# master_board_labrob.net
KiCad netlist of a schematic drawn in EAGLE
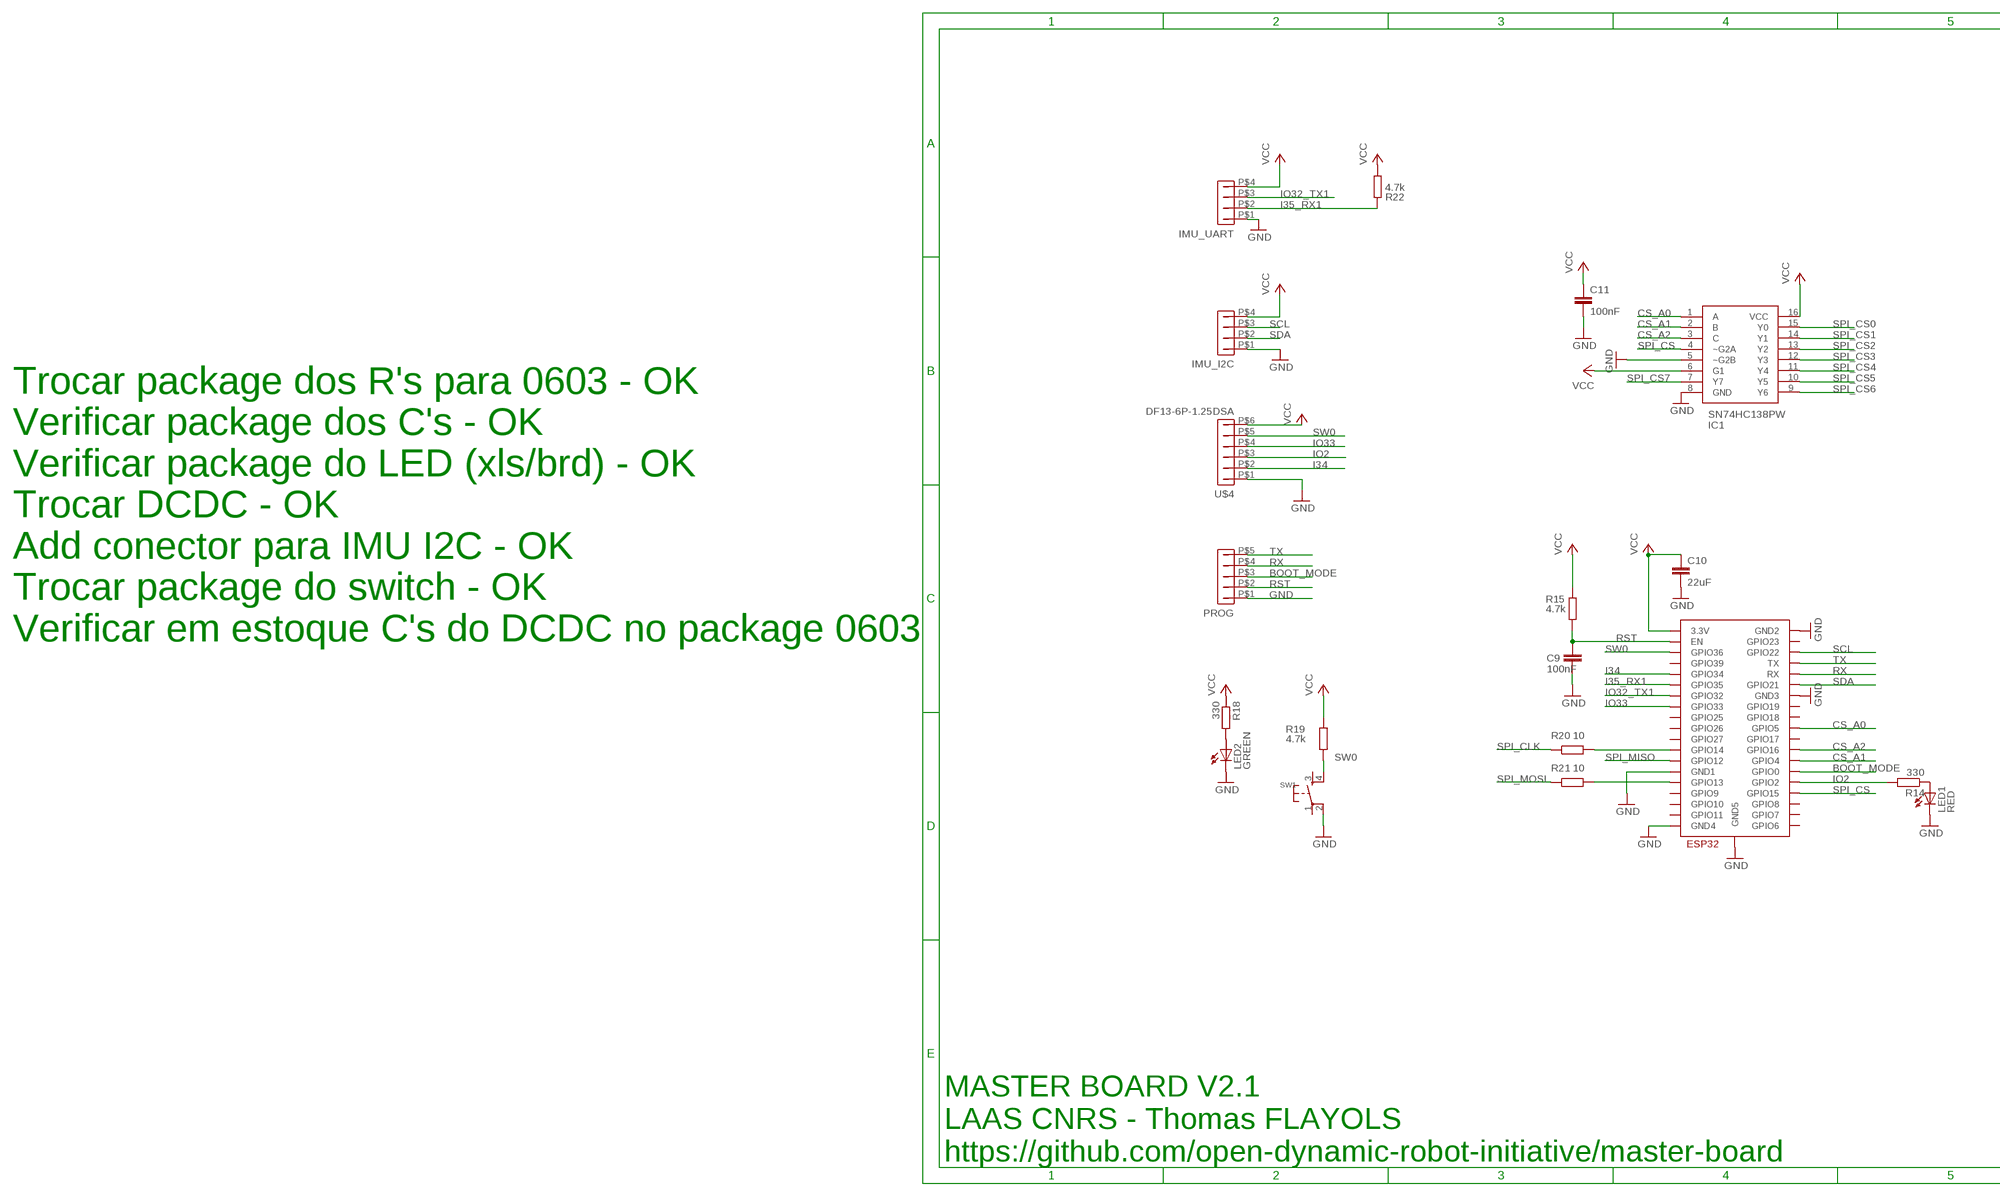
[diagram p0: schematic, sheet 1, part 1 of 2]
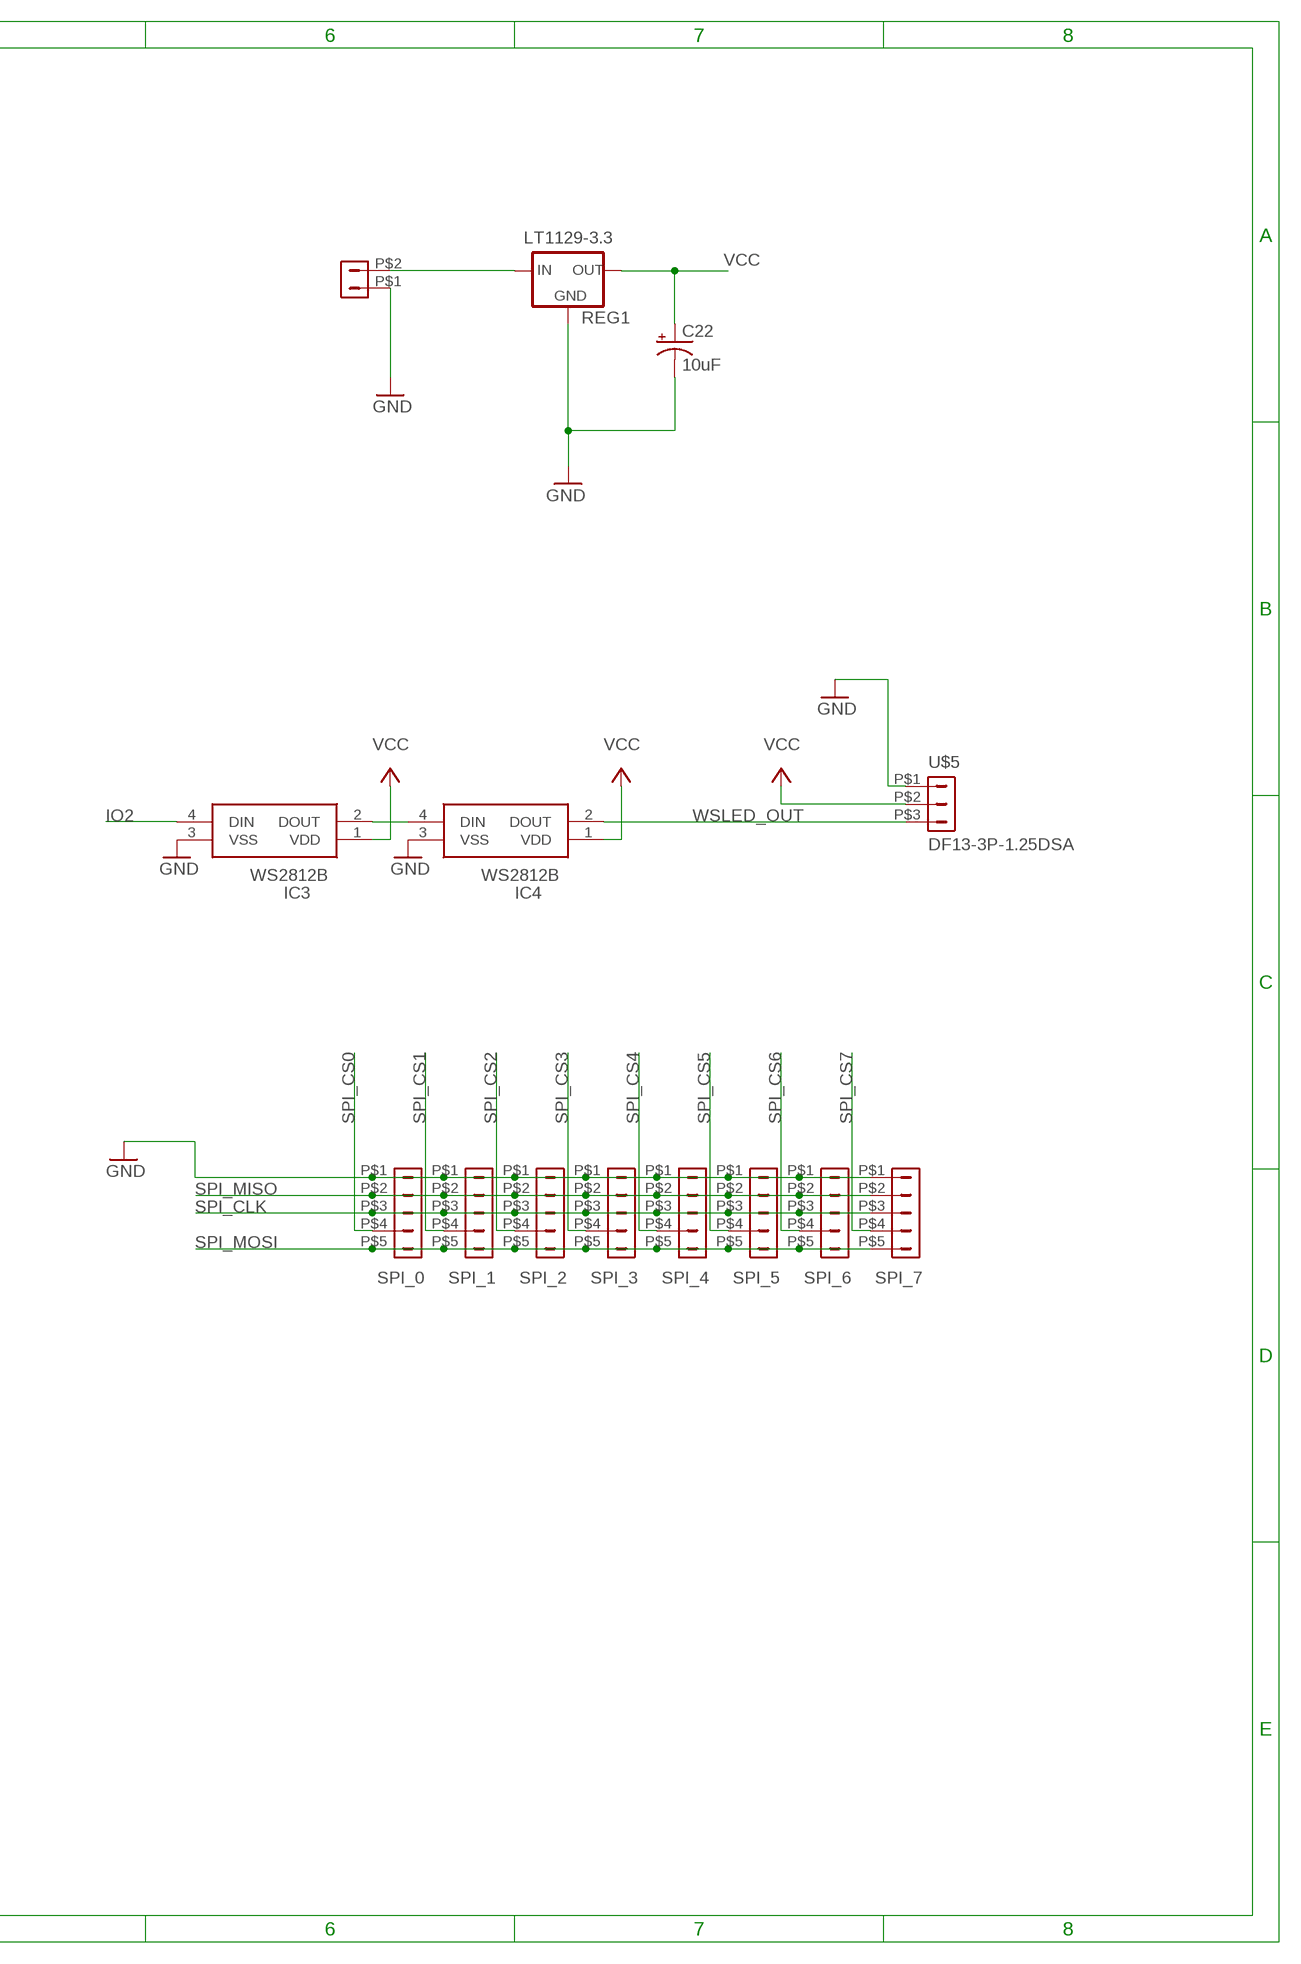
[diagram p1: schematic, sheet 1, part 2 of 2]

(export (version "E")
  (design (tool "Eeschema 10.0.6"))
  (components
    (comp (ref "C9")
      (value "100nF")
      (footprint "eagle-import:C0603")
      (fields (field (name "MANUFACTURER_PART_NUMBER") "CPL-CAP-X7R-0402-100NF-16V"))
      (libsource (lib "eagle-import") (part "C-EUC0603"))
    )
    (comp (ref "C10")
      (value "22uF")
      (footprint "eagle-import:C0805")
      (fields (field (name "MANUFACTURER_PART_NUMBER") "CPL-CAP-X5R-0805-22UF-6.3V"))
      (libsource (lib "eagle-import") (part "C-EUC0805"))
    )
    (comp (ref "C11")
      (value "100nF")
      (footprint "eagle-import:C0603")
      (fields (field (name "MANUFACTURER_PART_NUMBER") "CPL-CAP-X7R-0402-100NF-16V"))
      (libsource (lib "eagle-import") (part "C-EUC0603"))
    )
    (comp (ref "C22")
      (value "10uF")
      (footprint "eagle-import:C_6032-28R")
      (libsource (lib "eagle-import") (part "CPOL-USC/6032-28R"))
    )
    (comp (ref "IC1")
      (value "SN74HC138PW")
      (footprint "eagle-import:SOP65P640X120-16N")
      (fields (field (name "RS_PART_NUMBER") "6631928"))
      (libsource (lib "eagle-import") (part "SN74HC138PW"))
    )
    (comp (ref "IC3")
      (value "WS2812B")
      (footprint "eagle-import:WS2812B")
      (libsource (lib "eagle-import") (part "WS2812B"))
    )
    (comp (ref "IC4")
      (value "WS2812B")
      (footprint "eagle-import:WS2812B")
      (libsource (lib "eagle-import") (part "WS2812B"))
    )
    (comp (ref "IMU_I2C")
      (value "DF13-4P-1.25DSA")
      (footprint "eagle-import:DF13-4P-1.25DSA")
      (libsource (lib "eagle-import") (part "DF13-4P-1.25DSA"))
    )
    (comp (ref "IMU_UART")
      (value "DF13-4P-1.25DSA")
      (footprint "eagle-import:DF13-4P-1.25DSA")
      (libsource (lib "eagle-import") (part "DF13-4P-1.25DSA"))
    )
    (comp (ref "LED1")
      (value "RED")
      (footprint "eagle-import:CHIPLED_0603")
      (fields (field (name "MANUFACTURER_PART_NUMBER") "CPL-LED-0603-RED"))
      (libsource (lib "eagle-import") (part "LEDCHIPLED_0603"))
    )
    (comp (ref "LED2")
      (value "GREEN")
      (footprint "eagle-import:CHIPLED_0603")
      (fields (field (name "MANUFACTURER_PART_NUMBER") "CPL-LED-0603-GREEN"))
      (libsource (lib "eagle-import") (part "LEDCHIPLED_0603"))
    )
    (comp (ref "POWER")
      (value "DF13-2P-1.25DSA")
      (footprint "eagle-import:DF13-2P-1.25DSA")
      (fields (field (name "MANUFACTURER_PART_NUMBER") "DF13-3P-1.25DSA"))
      (libsource (lib "eagle-import") (part "DF13-2P-1.25DSA"))
    )
    (comp (ref "PROG")
      (value "DF13-5P-1.25DSA")
      (footprint "eagle-import:DF13-5P-1.25DSA")
      (libsource (lib "eagle-import") (part "DF13-5P-1.25DSA"))
    )
    (comp (ref "R14")
      (value "330")
      (footprint "eagle-import:R0603")
      (fields (field (name "MANUFACTURER_PART_NUMBER") "RC0402JR-13330RL"))
      (libsource (lib "eagle-import") (part "R-EU_R0603"))
    )
    (comp (ref "R15")
      (value "4.7k")
      (footprint "eagle-import:R0603")
      (fields (field (name "MANUFACTURER_PART_NUMBER") "CPL-RES-0402-4.7K-0.063W"))
      (libsource (lib "eagle-import") (part "R-EU_R0603"))
    )
    (comp (ref "R18")
      (value "330")
      (footprint "eagle-import:R0603")
      (fields (field (name "MANUFACTURER_PART_NUMBER") "RC0402JR-13330RL"))
      (libsource (lib "eagle-import") (part "R-EU_R0603"))
    )
    (comp (ref "R19")
      (value "4.7k")
      (footprint "eagle-import:R0603")
      (fields (field (name "MANUFACTURER_PART_NUMBER") "CPL-RES-0402-4.7K-0.063W"))
      (libsource (lib "eagle-import") (part "R-EU_R0603"))
    )
    (comp (ref "R20")
      (value "10")
      (footprint "eagle-import:R0603")
      (fields (field (name "MANUFACTURER_PART_NUMBER") "CPL-RES-0402-10-0.063W"))
      (libsource (lib "eagle-import") (part "R-EU_R0603"))
    )
    (comp (ref "R21")
      (value "10")
      (footprint "eagle-import:R0603")
      (fields (field (name "MANUFACTURER_PART_NUMBER") "CPL-RES-0402-10-0.063W"))
      (libsource (lib "eagle-import") (part "R-EU_R0603"))
    )
    (comp (ref "R22")
      (value "4.7k")
      (footprint "eagle-import:R0603")
      (fields (field (name "MANUFACTURER_PART_NUMBER") "CPL-RES-0402-4.7K-0.063W"))
      (libsource (lib "eagle-import") (part "R-EU_R0603"))
    )
    (comp (ref "REG1")
      (value "LT1129-3.3")
      (footprint "eagle-import:SOT223")
      (libsource (lib "eagle-import") (part "LT1129-3.3"))
    )
    (comp (ref "SPI_0")
      (value "DF13-5P-1.25DSA")
      (footprint "eagle-import:DF13-5P-1.25DSA")
      (libsource (lib "eagle-import") (part "DF13-5P-1.25DSA"))
    )
    (comp (ref "SPI_1")
      (value "DF13-5P-1.25DSA")
      (footprint "eagle-import:DF13-5P-1.25DSA")
      (libsource (lib "eagle-import") (part "DF13-5P-1.25DSA"))
    )
    (comp (ref "SPI_2")
      (value "DF13-5P-1.25DSA")
      (footprint "eagle-import:DF13-5P-1.25DSA")
      (libsource (lib "eagle-import") (part "DF13-5P-1.25DSA"))
    )
    (comp (ref "SPI_3")
      (value "DF13-5P-1.25DSA")
      (footprint "eagle-import:DF13-5P-1.25DSA")
      (libsource (lib "eagle-import") (part "DF13-5P-1.25DSA"))
    )
    (comp (ref "SPI_4")
      (value "DF13-5P-1.25DSA")
      (footprint "eagle-import:DF13-5P-1.25DSA")
      (libsource (lib "eagle-import") (part "DF13-5P-1.25DSA"))
    )
    (comp (ref "SPI_5")
      (value "DF13-5P-1.25DSA")
      (footprint "eagle-import:DF13-5P-1.25DSA")
      (libsource (lib "eagle-import") (part "DF13-5P-1.25DSA"))
    )
    (comp (ref "SPI_6")
      (value "DF13-5P-1.25DSA")
      (footprint "eagle-import:DF13-5P-1.25DSA")
      (libsource (lib "eagle-import") (part "DF13-5P-1.25DSA"))
    )
    (comp (ref "SPI_7")
      (value "DF13-5P-1.25DSA")
      (footprint "eagle-import:DF13-5P-1.25DSA")
      (libsource (lib "eagle-import") (part "DF13-5P-1.25DSA"))
    )
    (comp (ref "SW1")
      (value "B3U-1000P-2P-SMD")
      (footprint "eagle-import:DTSM-6")
      (fields (field (name "MANUFACTURER_PART_NUMBER") "B3U-1000P"))
      (libsource (lib "eagle-import") (part "DTSM-6"))
    )
    (comp (ref "U$1")
      (value "ESP32-WROOM")
      (footprint "eagle-import:ESP32-WROOM")
      (fields (field (name "MANUFACTURER_PART_NUMBER") "ESP32-WROOM-32D"))
      (libsource (lib "eagle-import") (part "ESP32-WROOM"))
    )
    (comp (ref "U$4")
      (value "DF13-6P-1.25DSA")
      (footprint "eagle-import:DF13-6P-1.25DSA")
      (libsource (lib "eagle-import") (part "DF13-6P-1.25DSA"))
    )
    (comp (ref "U$5")
      (value "DF13-3P-1.25DSA")
      (footprint "eagle-import:DF13-3P-1.25DSA")
      (libsource (lib "eagle-import") (part "DF13-3P-1.25DSA"))
    )
  )
  (nets
    (net (code "1") (name "/BOOT_MODE") (class "Default")
      (node (ref "PROG") (pin "P$3") (pinfunction "3_P$3") (pintype "passive"))
      (node (ref "U$1") (pin "IO0") (pinfunction "GPIO0_IO0") (pintype "bidirectional"))
    )
    (net (code "2") (name "/CS_A0") (class "Default")
      (node (ref "IC1") (pin "1") (pinfunction "A_1") (pintype "bidirectional"))
      (node (ref "U$1") (pin "IO5") (pinfunction "GPIO5_IO5") (pintype "bidirectional"))
    )
    (net (code "3") (name "/CS_A1") (class "Default")
      (node (ref "IC1") (pin "2") (pinfunction "B_2") (pintype "bidirectional"))
      (node (ref "U$1") (pin "IO4") (pinfunction "GPIO4_IO4") (pintype "bidirectional"))
    )
    (net (code "4") (name "/CS_A2") (class "Default")
      (node (ref "IC1") (pin "3") (pinfunction "C_3") (pintype "bidirectional"))
      (node (ref "U$1") (pin "IO16") (pinfunction "GPIO16_IO16") (pintype "bidirectional"))
    )
    (net (code "5") (name "/I34") (class "Default")
      (node (ref "U$1") (pin "IO34") (pinfunction "GPIO34_IO34") (pintype "bidirectional"))
      (node (ref "U$4") (pin "P$2") (pinfunction "2_P$2") (pintype "passive"))
    )
    (net (code "6") (name "/I35_RX1") (class "Default")
      (node (ref "IMU_UART") (pin "P$2") (pinfunction "2_P$2") (pintype "passive"))
      (node (ref "R22") (pin "2") (pinfunction "2_2") (pintype "passive"))
      (node (ref "U$1") (pin "IO35") (pinfunction "GPIO35_IO35") (pintype "bidirectional"))
    )
    (net (code "7") (name "/IO2") (class "Default")
      (node (ref "IC3") (pin "4") (pinfunction "DIN_4") (pintype "input"))
      (node (ref "R14") (pin "2") (pinfunction "2_2") (pintype "passive"))
      (node (ref "U$1") (pin "IO2") (pinfunction "GPIO2_IO2") (pintype "bidirectional"))
      (node (ref "U$4") (pin "P$3") (pinfunction "3_P$3") (pintype "passive"))
    )
    (net (code "8") (name "/IO32_TX1") (class "Default")
      (node (ref "IMU_UART") (pin "P$3") (pinfunction "3_P$3") (pintype "passive"))
      (node (ref "U$1") (pin "IO32") (pinfunction "GPIO32_IO32") (pintype "bidirectional"))
    )
    (net (code "9") (name "/IO33") (class "Default")
      (node (ref "U$1") (pin "IO33") (pinfunction "GPIO33_IO33") (pintype "bidirectional"))
      (node (ref "U$4") (pin "P$4") (pinfunction "4_P$4") (pintype "passive"))
    )
    (net (code "10") (name "/RST") (class "Default")
      (node (ref "C9") (pin "1") (pinfunction "1_1") (pintype "passive"))
      (node (ref "PROG") (pin "P$2") (pinfunction "2_P$2") (pintype "passive"))
      (node (ref "R15") (pin "1") (pinfunction "1_1") (pintype "passive"))
      (node (ref "U$1") (pin "EN") (pinfunction "EN_EN") (pintype "bidirectional"))
    )
    (net (code "11") (name "/RX") (class "Default")
      (node (ref "PROG") (pin "P$4") (pinfunction "4_P$4") (pintype "passive"))
      (node (ref "U$1") (pin "RX") (pinfunction "RX_RX") (pintype "bidirectional"))
    )
    (net (code "12") (name "/SCL") (class "Default")
      (node (ref "IMU_I2C") (pin "P$3") (pinfunction "3_P$3") (pintype "passive"))
      (node (ref "U$1") (pin "IO22") (pinfunction "GPIO22_IO22") (pintype "bidirectional"))
    )
    (net (code "13") (name "/SDA") (class "Default")
      (node (ref "IMU_I2C") (pin "P$2") (pinfunction "2_P$2") (pintype "passive"))
      (node (ref "U$1") (pin "IO21") (pinfunction "GPIO21_IO21") (pintype "bidirectional"))
    )
    (net (code "14") (name "/SPI_CLK") (class "Default")
      (node (ref "R20") (pin "1") (pinfunction "1_1") (pintype "passive"))
      (node (ref "SPI_0") (pin "P$3") (pinfunction "3_P$3") (pintype "passive"))
      (node (ref "SPI_1") (pin "P$3") (pinfunction "3_P$3") (pintype "passive"))
      (node (ref "SPI_2") (pin "P$3") (pinfunction "3_P$3") (pintype "passive"))
      (node (ref "SPI_3") (pin "P$3") (pinfunction "3_P$3") (pintype "passive"))
      (node (ref "SPI_4") (pin "P$3") (pinfunction "3_P$3") (pintype "passive"))
      (node (ref "SPI_5") (pin "P$3") (pinfunction "3_P$3") (pintype "passive"))
      (node (ref "SPI_6") (pin "P$3") (pinfunction "3_P$3") (pintype "passive"))
      (node (ref "SPI_7") (pin "P$3") (pinfunction "3_P$3") (pintype "passive"))
    )
    (net (code "15") (name "/SPI_CS") (class "Default")
      (node (ref "IC1") (pin "4") (pinfunction "~{G2A}_4") (pintype "bidirectional"))
      (node (ref "U$1") (pin "IO15") (pinfunction "GPIO15_IO15") (pintype "bidirectional"))
    )
    (net (code "16") (name "/SPI_CS0") (class "Default")
      (node (ref "IC1") (pin "15") (pinfunction "Y0_15") (pintype "bidirectional"))
      (node (ref "SPI_0") (pin "P$4") (pinfunction "4_P$4") (pintype "passive"))
    )
    (net (code "17") (name "/SPI_CS1") (class "Default")
      (node (ref "IC1") (pin "14") (pinfunction "Y1_14") (pintype "bidirectional"))
      (node (ref "SPI_1") (pin "P$4") (pinfunction "4_P$4") (pintype "passive"))
    )
    (net (code "18") (name "/SPI_CS2") (class "Default")
      (node (ref "IC1") (pin "13") (pinfunction "Y2_13") (pintype "bidirectional"))
      (node (ref "SPI_2") (pin "P$4") (pinfunction "4_P$4") (pintype "passive"))
    )
    (net (code "19") (name "/SPI_CS3") (class "Default")
      (node (ref "IC1") (pin "12") (pinfunction "Y3_12") (pintype "bidirectional"))
      (node (ref "SPI_3") (pin "P$4") (pinfunction "4_P$4") (pintype "passive"))
    )
    (net (code "20") (name "/SPI_CS4") (class "Default")
      (node (ref "IC1") (pin "11") (pinfunction "Y4_11") (pintype "bidirectional"))
      (node (ref "SPI_4") (pin "P$4") (pinfunction "4_P$4") (pintype "passive"))
    )
    (net (code "21") (name "/SPI_CS5") (class "Default")
      (node (ref "IC1") (pin "10") (pinfunction "Y5_10") (pintype "bidirectional"))
      (node (ref "SPI_5") (pin "P$4") (pinfunction "4_P$4") (pintype "passive"))
    )
    (net (code "22") (name "/SPI_CS6") (class "Default")
      (node (ref "IC1") (pin "9") (pinfunction "Y6_9") (pintype "bidirectional"))
      (node (ref "SPI_6") (pin "P$4") (pinfunction "4_P$4") (pintype "passive"))
    )
    (net (code "23") (name "/SPI_CS7") (class "Default")
      (node (ref "IC1") (pin "7") (pinfunction "Y7_7") (pintype "bidirectional"))
      (node (ref "SPI_7") (pin "P$4") (pinfunction "4_P$4") (pintype "passive"))
    )
    (net (code "24") (name "/SPI_MISO") (class "Default")
      (node (ref "SPI_0") (pin "P$2") (pinfunction "2_P$2") (pintype "passive"))
      (node (ref "SPI_1") (pin "P$2") (pinfunction "2_P$2") (pintype "passive"))
      (node (ref "SPI_2") (pin "P$2") (pinfunction "2_P$2") (pintype "passive"))
      (node (ref "SPI_3") (pin "P$2") (pinfunction "2_P$2") (pintype "passive"))
      (node (ref "SPI_4") (pin "P$2") (pinfunction "2_P$2") (pintype "passive"))
      (node (ref "SPI_5") (pin "P$2") (pinfunction "2_P$2") (pintype "passive"))
      (node (ref "SPI_6") (pin "P$2") (pinfunction "2_P$2") (pintype "passive"))
      (node (ref "SPI_7") (pin "P$2") (pinfunction "2_P$2") (pintype "passive"))
      (node (ref "U$1") (pin "IO12") (pinfunction "GPIO12_IO12") (pintype "bidirectional"))
    )
    (net (code "25") (name "/SPI_MOSI") (class "Default")
      (node (ref "R21") (pin "1") (pinfunction "1_1") (pintype "passive"))
      (node (ref "SPI_0") (pin "P$5") (pinfunction "5_P$5") (pintype "passive"))
      (node (ref "SPI_1") (pin "P$5") (pinfunction "5_P$5") (pintype "passive"))
      (node (ref "SPI_2") (pin "P$5") (pinfunction "5_P$5") (pintype "passive"))
      (node (ref "SPI_3") (pin "P$5") (pinfunction "5_P$5") (pintype "passive"))
      (node (ref "SPI_4") (pin "P$5") (pinfunction "5_P$5") (pintype "passive"))
      (node (ref "SPI_5") (pin "P$5") (pinfunction "5_P$5") (pintype "passive"))
      (node (ref "SPI_6") (pin "P$5") (pinfunction "5_P$5") (pintype "passive"))
      (node (ref "SPI_7") (pin "P$5") (pinfunction "5_P$5") (pintype "passive"))
    )
    (net (code "26") (name "/SW0") (class "Default")
      (node (ref "R19") (pin "1") (pinfunction "1_1") (pintype "passive"))
      (node (ref "SW1") (pin "4") (pinfunction "4_4") (pintype "passive"))
      (node (ref "U$1") (pin "SENSOR_VP") (pinfunction "GPIO36_SENSOR_VP") (pintype "bidirectional"))
      (node (ref "U$4") (pin "P$5") (pinfunction "5_P$5") (pintype "passive"))
    )
    (net (code "27") (name "/TX") (class "Default")
      (node (ref "PROG") (pin "P$5") (pinfunction "5_P$5") (pintype "passive"))
      (node (ref "U$1") (pin "TX") (pinfunction "TX_TX") (pintype "bidirectional"))
    )
    (net (code "28") (name "/WSLED_OUT") (class "Default")
      (node (ref "IC4") (pin "2") (pinfunction "DOUT_2") (pintype "output"))
      (node (ref "U$5") (pin "P$3") (pinfunction "3_P$3") (pintype "passive"))
    )
    (net (code "29") (name "GND") (class "Default")
      (node (ref "C10") (pin "2") (pinfunction "2_2") (pintype "passive"))
      (node (ref "C11") (pin "2") (pinfunction "2_2") (pintype "passive"))
      (node (ref "C22") (pin "-") (pinfunction "-_-") (pintype "passive"))
      (node (ref "C9") (pin "2") (pinfunction "2_2") (pintype "passive"))
      (node (ref "IC1") (pin "5") (pinfunction "~{G2B}_5") (pintype "bidirectional"))
      (node (ref "IC1") (pin "8") (pinfunction "GND_8") (pintype "bidirectional"))
      (node (ref "IC3") (pin "3") (pinfunction "VSS_3") (pintype "power_in"))
      (node (ref "IC4") (pin "3") (pinfunction "VSS_3") (pintype "power_in"))
      (node (ref "IMU_I2C") (pin "P$1") (pinfunction "1_P$1") (pintype "passive"))
      (node (ref "IMU_UART") (pin "P$1") (pinfunction "1_P$1") (pintype "passive"))
      (node (ref "LED1") (pin "C") (pinfunction "C_C") (pintype "passive"))
      (node (ref "LED2") (pin "C") (pinfunction "C_C") (pintype "passive"))
      (node (ref "POWER") (pin "P$1") (pinfunction "1_P$1") (pintype "passive"))
      (node (ref "PROG") (pin "P$1") (pinfunction "1_P$1") (pintype "passive"))
      (node (ref "REG1") (pin "2") (pinfunction "GND_2") (pintype "input"))
      (node (ref "REG1") (pin "TAB") (pinfunction "GND_TAB") (pintype "input"))
      (node (ref "SPI_0") (pin "P$1") (pinfunction "1_P$1") (pintype "passive"))
      (node (ref "SPI_1") (pin "P$1") (pinfunction "1_P$1") (pintype "passive"))
      (node (ref "SPI_2") (pin "P$1") (pinfunction "1_P$1") (pintype "passive"))
      (node (ref "SPI_3") (pin "P$1") (pinfunction "1_P$1") (pintype "passive"))
      (node (ref "SPI_4") (pin "P$1") (pinfunction "1_P$1") (pintype "passive"))
      (node (ref "SPI_5") (pin "P$1") (pinfunction "1_P$1") (pintype "passive"))
      (node (ref "SPI_6") (pin "P$1") (pinfunction "1_P$1") (pintype "passive"))
      (node (ref "SPI_7") (pin "P$1") (pinfunction "1_P$1") (pintype "passive"))
      (node (ref "SW1") (pin "2") (pinfunction "2_2") (pintype "passive"))
      (node (ref "U$1") (pin "GND1") (pinfunction "GND1_GND1") (pintype "bidirectional"))
      (node (ref "U$1") (pin "GND2") (pinfunction "GND2_GND2") (pintype "bidirectional"))
      (node (ref "U$1") (pin "GND3") (pinfunction "GND3_GND3") (pintype "bidirectional"))
      (node (ref "U$1") (pin "GND4") (pinfunction "GND4_GND4") (pintype "bidirectional"))
      (node (ref "U$1") (pin "GND5") (pinfunction "GND5_GND5") (pintype "bidirectional"))
      (node (ref "U$4") (pin "P$1") (pinfunction "1_P$1") (pintype "passive"))
      (node (ref "U$5") (pin "P$1") (pinfunction "1_P$1") (pintype "passive"))
    )
    (net (code "30") (name "Net-(IC3-DOUT)") (class "Default")
      (node (ref "IC3") (pin "2") (pinfunction "DOUT_2") (pintype "output"))
      (node (ref "IC4") (pin "4") (pinfunction "DIN_4") (pintype "input"))
    )
    (net (code "31") (name "Net-(LED1-PadA)") (class "Default")
      (node (ref "LED1") (pin "A") (pinfunction "A_A") (pintype "passive"))
      (node (ref "R14") (pin "1") (pinfunction "1_1") (pintype "passive"))
    )
    (net (code "32") (name "Net-(LED2-PadA)") (class "Default")
      (node (ref "LED2") (pin "A") (pinfunction "A_A") (pintype "passive"))
      (node (ref "R18") (pin "2") (pinfunction "2_2") (pintype "passive"))
    )
    (net (code "33") (name "Net-(POWER-2)") (class "Default")
      (node (ref "POWER") (pin "P$2") (pinfunction "2_P$2") (pintype "passive"))
      (node (ref "REG1") (pin "1") (pinfunction "IN_1") (pintype "input"))
    )
    (net (code "34") (name "Net-(U$1-GPIO13)") (class "Default")
      (node (ref "R21") (pin "2") (pinfunction "2_2") (pintype "passive"))
      (node (ref "U$1") (pin "IO13") (pinfunction "GPIO13_IO13") (pintype "bidirectional"))
    )
    (net (code "35") (name "Net-(U$1-GPIO14)") (class "Default")
      (node (ref "R20") (pin "2") (pinfunction "2_2") (pintype "passive"))
      (node (ref "U$1") (pin "IO14") (pinfunction "GPIO14_IO14") (pintype "bidirectional"))
    )
    (net (code "36") (name "VCC") (class "Default")
      (node (ref "C10") (pin "1") (pinfunction "1_1") (pintype "passive"))
      (node (ref "C11") (pin "1") (pinfunction "1_1") (pintype "passive"))
      (node (ref "C22") (pin "+") (pinfunction "+_+") (pintype "passive"))
      (node (ref "IC1") (pin "16") (pinfunction "VCC_16") (pintype "bidirectional"))
      (node (ref "IC1") (pin "6") (pinfunction "G1_6") (pintype "bidirectional"))
      (node (ref "IC3") (pin "1") (pinfunction "VDD_1") (pintype "power_in"))
      (node (ref "IC4") (pin "1") (pinfunction "VDD_1") (pintype "power_in"))
      (node (ref "IMU_I2C") (pin "P$4") (pinfunction "4_P$4") (pintype "passive"))
      (node (ref "IMU_UART") (pin "P$4") (pinfunction "4_P$4") (pintype "passive"))
      (node (ref "R15") (pin "2") (pinfunction "2_2") (pintype "passive"))
      (node (ref "R18") (pin "1") (pinfunction "1_1") (pintype "passive"))
      (node (ref "R19") (pin "2") (pinfunction "2_2") (pintype "passive"))
      (node (ref "R22") (pin "1") (pinfunction "1_1") (pintype "passive"))
      (node (ref "REG1") (pin "3") (pinfunction "OUT_3") (pintype "passive"))
      (node (ref "U$1") (pin "3V3") (pinfunction "3.3V_3V3") (pintype "bidirectional"))
      (node (ref "U$4") (pin "P$6") (pinfunction "6_P$6") (pintype "passive"))
      (node (ref "U$5") (pin "P$2") (pinfunction "2_P$2") (pintype "passive"))
    )
    (net (code "37") (name "unconnected-(SW1-Pad1)") (class "Default")
      (node (ref "SW1") (pin "1") (pinfunction "1_1") (pintype "passive"))
    )
    (net (code "38") (name "unconnected-(SW1-Pad3)") (class "Default")
      (node (ref "SW1") (pin "3") (pinfunction "3_3") (pintype "passive"))
    )
    (net (code "39") (name "unconnected-(U$1-GPIO6-PadCLK)") (class "Default")
      (node (ref "U$1") (pin "CLK") (pinfunction "GPIO6_CLK") (pintype "bidirectional"))
    )
    (net (code "40") (name "unconnected-(U$1-GPIO7-PadSD0)") (class "Default")
      (node (ref "U$1") (pin "SD0") (pinfunction "GPIO7_SD0") (pintype "bidirectional"))
    )
    (net (code "41") (name "unconnected-(U$1-GPIO8-PadSD1)") (class "Default")
      (node (ref "U$1") (pin "SD1") (pinfunction "GPIO8_SD1") (pintype "bidirectional"))
    )
    (net (code "42") (name "unconnected-(U$1-GPIO9-PadSD2)") (class "Default")
      (node (ref "U$1") (pin "SD2") (pinfunction "GPIO9_SD2") (pintype "bidirectional"))
    )
    (net (code "43") (name "unconnected-(U$1-GPIO10-PadSD3)") (class "Default")
      (node (ref "U$1") (pin "SD3") (pinfunction "GPIO10_SD3") (pintype "bidirectional"))
    )
    (net (code "44") (name "unconnected-(U$1-GPIO11-PadCMD)") (class "Default")
      (node (ref "U$1") (pin "CMD") (pinfunction "GPIO11_CMD") (pintype "bidirectional"))
    )
    (net (code "45") (name "unconnected-(U$1-GPIO17-PadIO17)") (class "Default")
      (node (ref "U$1") (pin "IO17") (pinfunction "GPIO17_IO17") (pintype "bidirectional"))
    )
    (net (code "46") (name "unconnected-(U$1-GPIO18-PadIO18)") (class "Default")
      (node (ref "U$1") (pin "IO18") (pinfunction "GPIO18_IO18") (pintype "bidirectional"))
    )
    (net (code "47") (name "unconnected-(U$1-GPIO19-PadIO19)") (class "Default")
      (node (ref "U$1") (pin "IO19") (pinfunction "GPIO19_IO19") (pintype "bidirectional"))
    )
    (net (code "48") (name "unconnected-(U$1-GPIO23-PadIO23)") (class "Default")
      (node (ref "U$1") (pin "IO23") (pinfunction "GPIO23_IO23") (pintype "bidirectional"))
    )
    (net (code "49") (name "unconnected-(U$1-GPIO25-PadIO25)") (class "Default")
      (node (ref "U$1") (pin "IO25") (pinfunction "GPIO25_IO25") (pintype "bidirectional"))
    )
    (net (code "50") (name "unconnected-(U$1-GPIO26-PadIO26)") (class "Default")
      (node (ref "U$1") (pin "IO26") (pinfunction "GPIO26_IO26") (pintype "bidirectional"))
    )
    (net (code "51") (name "unconnected-(U$1-GPIO27-PadIO27)") (class "Default")
      (node (ref "U$1") (pin "IO27") (pinfunction "GPIO27_IO27") (pintype "bidirectional"))
    )
    (net (code "52") (name "unconnected-(U$1-GPIO39-PadSENSOR_VN)") (class "Default")
      (node (ref "U$1") (pin "SENSOR_VN") (pinfunction "GPIO39_SENSOR_VN") (pintype "bidirectional"))
    )
  )
)
